# 8pins_together.net
KiCad netlist of a schematic drawn in Altium Designer
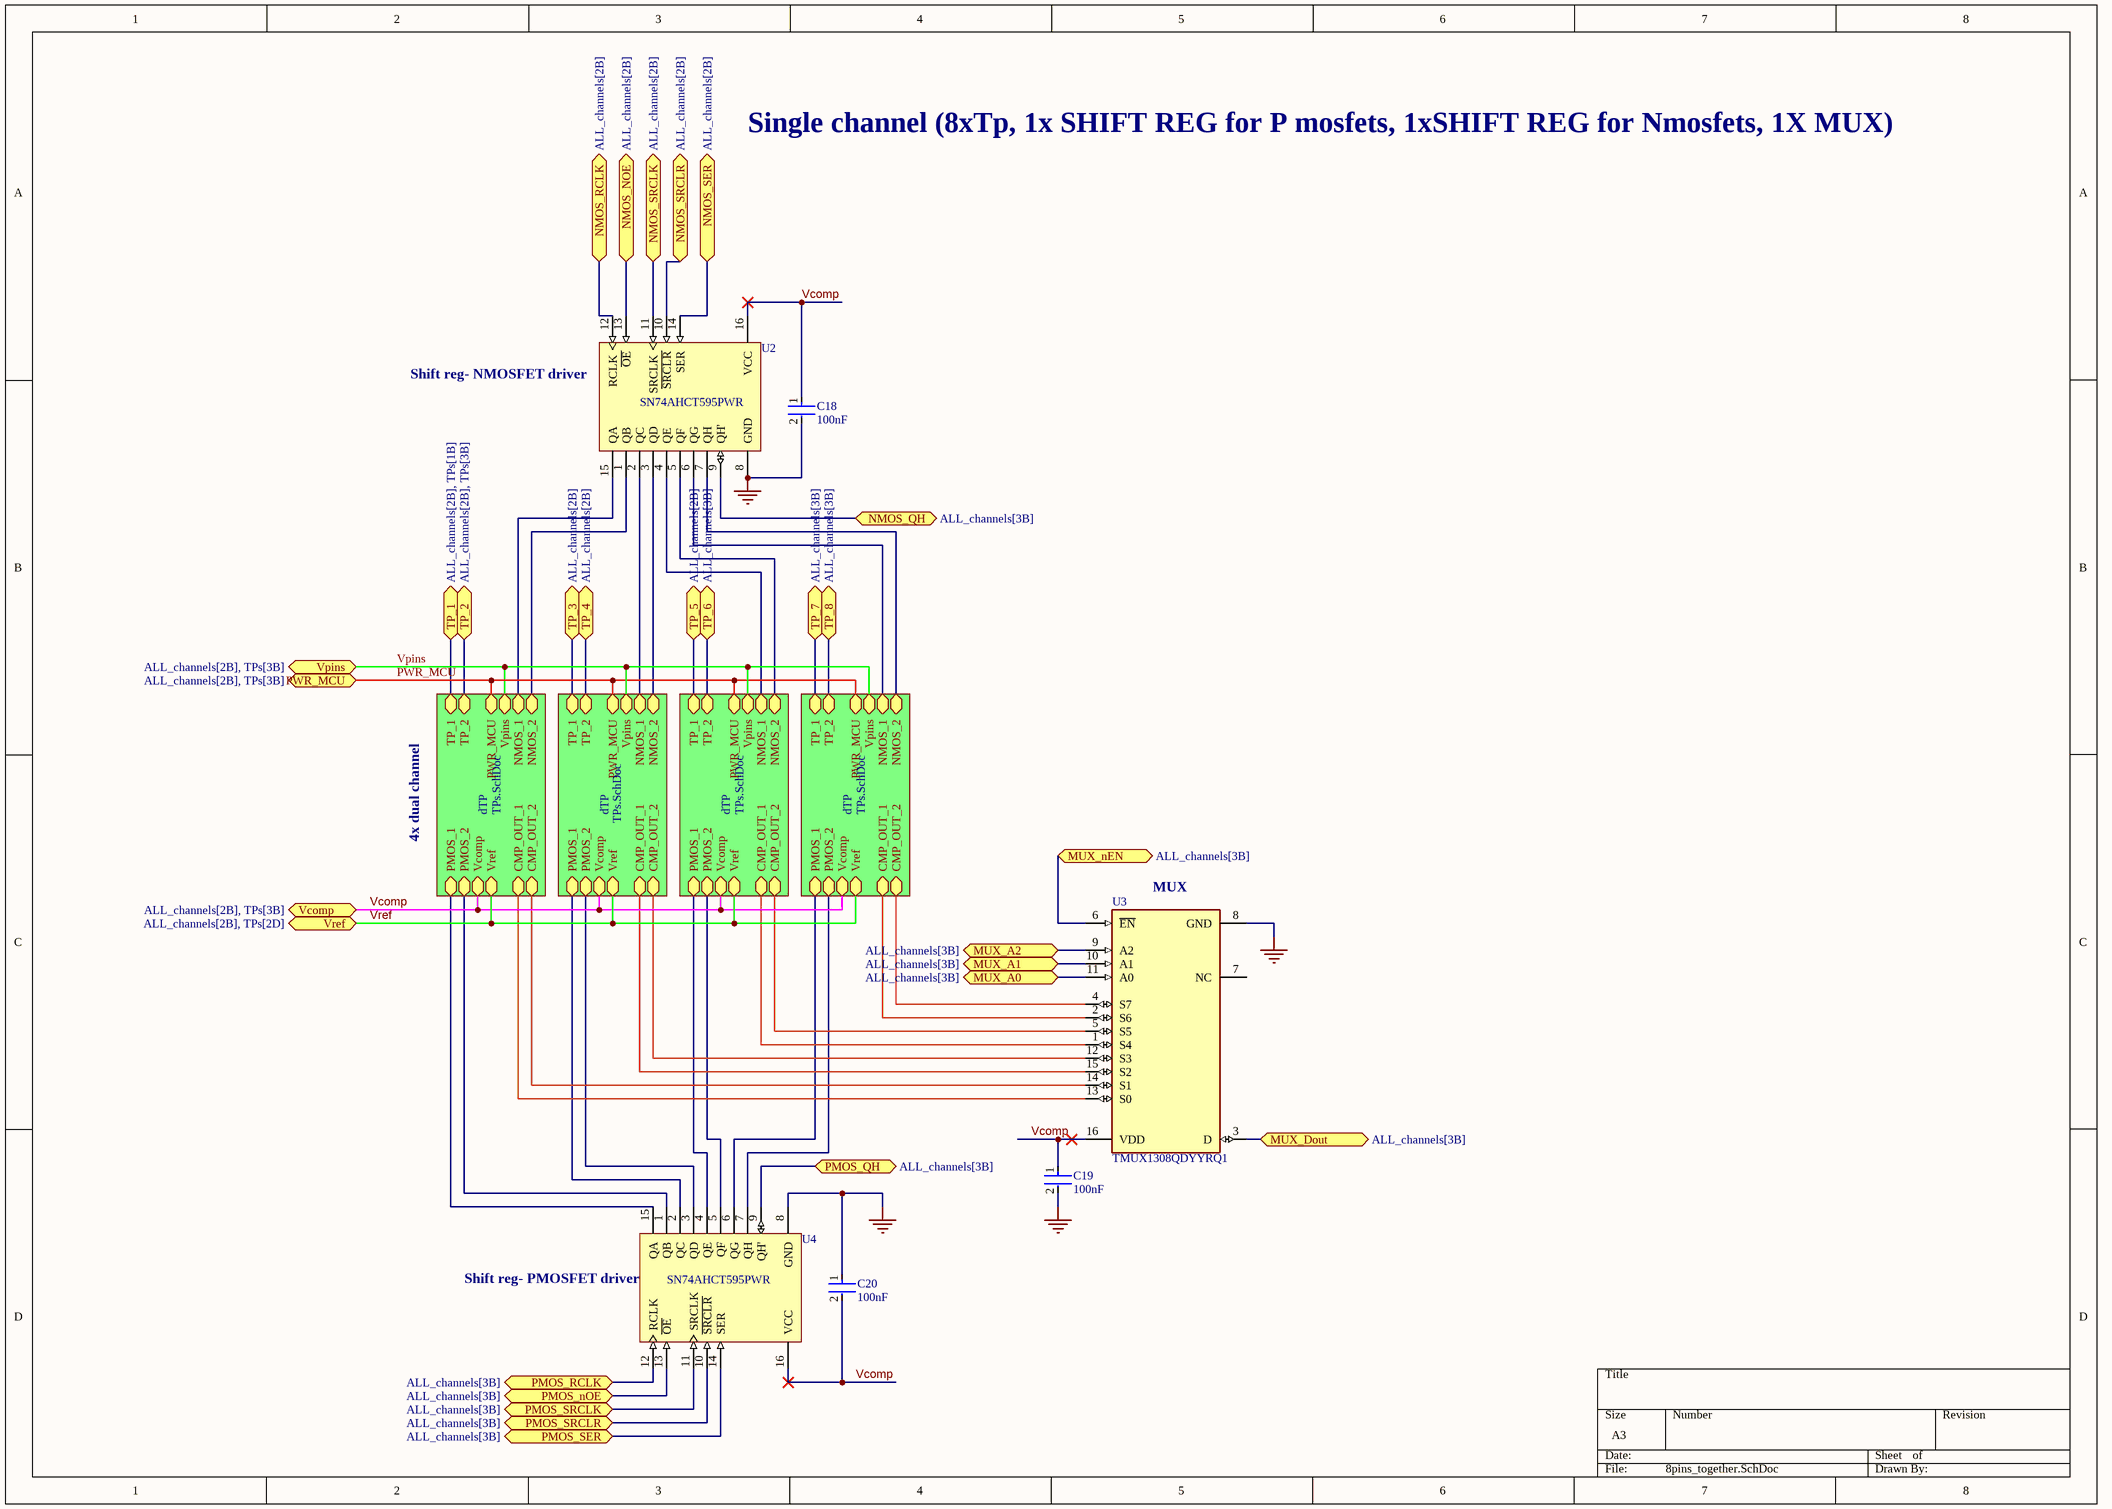
[diagram p0: 8pins_together.SchDoc]

(export (version "E")
  (design (tool "Eeschema 10.0.6"))
  (components
    (comp (ref "C18")
      (value "100nF")
      (footprint "PcbLib1:0402 CAP")
      (description "Cap Ceramic 0.1uF 25V X7R 10% Pad SMD 0402 125C T/R")
      (fields
        (field (name "MANUFACTURER") "Kemet")
        (field (name "MANUFACTURER PART NUMBER") "C0402C104K3RACTU")
      )
      (libsource (lib "Schlib1") (part "Capacitor 0402 25V"))
    )
    (comp (ref "C19")
      (value "100nF")
      (footprint "PcbLib1:0402 CAP")
      (description "Cap Ceramic 0.1uF 25V X7R 10% Pad SMD 0402 125C T/R")
      (fields
        (field (name "MANUFACTURER") "Kemet")
        (field (name "MANUFACTURER PART NUMBER") "C0402C104K3RACTU")
      )
      (libsource (lib "Schlib1") (part "Capacitor 0402 25V"))
    )
    (comp (ref "C20")
      (value "100nF")
      (footprint "PcbLib1:0402 CAP")
      (description "Cap Ceramic 0.1uF 25V X7R 10% Pad SMD 0402 125C T/R")
      (fields
        (field (name "MANUFACTURER") "Kemet")
        (field (name "MANUFACTURER PART NUMBER") "C0402C104K3RACTU")
      )
      (libsource (lib "Schlib1") (part "Capacitor 0402 25V"))
    )
    (comp (ref "U2")
      (value "SN74AHCT595PWR")
      (footprint "PcbLib1:SSOT16")
      (description "8-Bit Shift Registers With 3-State Output Registers, PW0016A, LARGE T&R")
      (fields
        (field (name "GENERIC PART NUMBER") "SN74AHCT595")
        (field (name "MANUFACTURER") "Texas Instruments")
      )
      (libsource (lib "") (part "SN74AHCT595PWR_1"))
    )
    (comp (ref "U3")
      (value "TMUX1308QDYYRQ1")
      (footprint "PcbLib1:FP-DYY0016A-MFG")
      (description "AUTOMOTIVE, 5-V, 8:1, 1-CHANNEL")
      (libsource (lib "Schlib1") (part "TMUX1308QDYYRQ1"))
    )
    (comp (ref "U4")
      (value "SN74AHCT595PWR")
      (footprint "PcbLib1:SSOT16")
      (description "8-Bit Shift Registers With 3-State Output Registers, PW0016A, LARGE T&R")
      (fields
        (field (name "GENERIC PART NUMBER") "SN74AHCT595")
        (field (name "MANUFACTURER") "Texas Instruments")
      )
      (libsource (lib "Schlib1") (part "SN74AHCT595PWR"))
    )
  )
  (nets
    (net (code "1") (name "/CMP_OUT_1") (class "Default")
      (node (ref "U3") (pin "1") (pinfunction "S4_1") (pintype "bidirectional"))
    )
    (net (code "2") (name "/CMP_OUT_1_1") (class "Default")
      (node (ref "U3") (pin "2") (pinfunction "S6_2") (pintype "bidirectional"))
    )
    (net (code "3") (name "/CMP_OUT_1_2") (class "Default")
      (node (ref "U3") (pin "13") (pinfunction "S0_13") (pintype "bidirectional"))
    )
    (net (code "4") (name "/CMP_OUT_1_3") (class "Default")
      (node (ref "U3") (pin "15") (pinfunction "S2_15") (pintype "bidirectional"))
    )
    (net (code "5") (name "/CMP_OUT_2") (class "Default")
      (node (ref "U3") (pin "5") (pinfunction "S5_5") (pintype "bidirectional"))
    )
    (net (code "6") (name "/CMP_OUT_2_1") (class "Default")
      (node (ref "U3") (pin "4") (pinfunction "S7_4") (pintype "bidirectional"))
    )
    (net (code "7") (name "/CMP_OUT_2_2") (class "Default")
      (node (ref "U3") (pin "14") (pinfunction "S1_14") (pintype "bidirectional"))
    )
    (net (code "8") (name "/CMP_OUT_2_3") (class "Default")
      (node (ref "U3") (pin "12") (pinfunction "S3_12") (pintype "bidirectional"))
    )
    (net (code "9") (name "/MUX_A0") (class "Default")
      (node (ref "U3") (pin "11") (pinfunction "A0_11") (pintype "input"))
    )
    (net (code "10") (name "/MUX_A1") (class "Default")
      (node (ref "U3") (pin "10") (pinfunction "A1_10") (pintype "input"))
    )
    (net (code "11") (name "/MUX_A2") (class "Default")
      (node (ref "U3") (pin "9") (pinfunction "A2_9") (pintype "input"))
    )
    (net (code "12") (name "/MUX_Dout") (class "Default")
      (node (ref "U3") (pin "3") (pinfunction "D_3") (pintype "bidirectional"))
    )
    (net (code "13") (name "/MUX_nEN") (class "Default")
      (node (ref "U3") (pin "6") (pinfunction "~{EN}_6") (pintype "input"))
    )
    (net (code "14") (name "/NMOS_1") (class "Default")
      (node (ref "U2") (pin "2") (pinfunction "QC_2") (pintype "tri_state"))
    )
    (net (code "15") (name "/NMOS_1_1") (class "Default")
      (node (ref "U2") (pin "4") (pinfunction "QE_4") (pintype "tri_state"))
    )
    (net (code "16") (name "/NMOS_1_2") (class "Default")
      (node (ref "U2") (pin "6") (pinfunction "QG_6") (pintype "tri_state"))
    )
    (net (code "17") (name "/NMOS_1_3") (class "Default")
      (node (ref "U2") (pin "15") (pinfunction "QA_15") (pintype "tri_state"))
    )
    (net (code "18") (name "/NMOS_2") (class "Default")
      (node (ref "U2") (pin "3") (pinfunction "QD_3") (pintype "tri_state"))
    )
    (net (code "19") (name "/NMOS_2_1") (class "Default")
      (node (ref "U2") (pin "5") (pinfunction "QF_5") (pintype "tri_state"))
    )
    (net (code "20") (name "/NMOS_2_2") (class "Default")
      (node (ref "U2") (pin "7") (pinfunction "QH_7") (pintype "tri_state"))
    )
    (net (code "21") (name "/NMOS_2_3") (class "Default")
      (node (ref "U2") (pin "1") (pinfunction "QB_1") (pintype "tri_state"))
    )
    (net (code "22") (name "/NMOS_NOE") (class "Default")
      (node (ref "U2") (pin "13") (pinfunction "~{OE}_13") (pintype "input"))
    )
    (net (code "23") (name "/NMOS_QH") (class "Default")
      (node (ref "U2") (pin "9") (pinfunction "QH'_9") (pintype "bidirectional"))
    )
    (net (code "24") (name "/NMOS_RCLK") (class "Default")
      (node (ref "U2") (pin "12") (pinfunction "RCLK_12") (pintype "input"))
    )
    (net (code "25") (name "/NMOS_SER") (class "Default")
      (node (ref "U2") (pin "14") (pinfunction "SER_14") (pintype "input"))
    )
    (net (code "26") (name "/NMOS_SRCLK") (class "Default")
      (node (ref "U2") (pin "11") (pinfunction "SRCLK_11") (pintype "input"))
    )
    (net (code "27") (name "/NMOS_SRCLR") (class "Default")
      (node (ref "U2") (pin "10") (pinfunction "~{SRCLR}_10") (pintype "input"))
    )
    (net (code "28") (name "/PMOS_1") (class "Default")
      (node (ref "U4") (pin "4") (pinfunction "QE_4") (pintype "tri_state"))
    )
    (net (code "29") (name "/PMOS_1_1") (class "Default")
      (node (ref "U4") (pin "6") (pinfunction "QG_6") (pintype "tri_state"))
    )
    (net (code "30") (name "/PMOS_1_2") (class "Default")
      (node (ref "U4") (pin "15") (pinfunction "QA_15") (pintype "tri_state"))
    )
    (net (code "31") (name "/PMOS_1_3") (class "Default")
      (node (ref "U4") (pin "2") (pinfunction "QC_2") (pintype "tri_state"))
    )
    (net (code "32") (name "/PMOS_2") (class "Default")
      (node (ref "U4") (pin "5") (pinfunction "QF_5") (pintype "tri_state"))
    )
    (net (code "33") (name "/PMOS_2_1") (class "Default")
      (node (ref "U4") (pin "7") (pinfunction "QH_7") (pintype "tri_state"))
    )
    (net (code "34") (name "/PMOS_2_2") (class "Default")
      (node (ref "U4") (pin "1") (pinfunction "QB_1") (pintype "tri_state"))
    )
    (net (code "35") (name "/PMOS_2_3") (class "Default")
      (node (ref "U4") (pin "3") (pinfunction "QD_3") (pintype "tri_state"))
    )
    (net (code "36") (name "/PMOS_QH") (class "Default")
      (node (ref "U4") (pin "9") (pinfunction "QH'_9") (pintype "bidirectional"))
    )
    (net (code "37") (name "/PMOS_RCLK") (class "Default")
      (node (ref "U4") (pin "12") (pinfunction "RCLK_12") (pintype "input"))
    )
    (net (code "38") (name "/PMOS_SER") (class "Default")
      (node (ref "U4") (pin "14") (pinfunction "SER_14") (pintype "input"))
    )
    (net (code "39") (name "/PMOS_SRCLK") (class "Default")
      (node (ref "U4") (pin "11") (pinfunction "SRCLK_11") (pintype "input"))
    )
    (net (code "40") (name "/PMOS_SRCLR") (class "Default")
      (node (ref "U4") (pin "10") (pinfunction "~{SRCLR}_10") (pintype "input"))
    )
    (net (code "41") (name "/PMOS_nOE") (class "Default")
      (node (ref "U4") (pin "13") (pinfunction "~{OE}_13") (pintype "input"))
    )
    (net (code "51") (name "/Vcomp") (class "Default")
      (node (ref "C18") (pin "1") (pinfunction "1_1") (pintype "passive"))
      (node (ref "C19") (pin "1") (pinfunction "1_1") (pintype "passive"))
      (node (ref "C20") (pin "2") (pinfunction "2_2") (pintype "passive"))
      (node (ref "U2") (pin "16") (pinfunction "VCC_16") (pintype "power_in"))
      (node (ref "U3") (pin "16") (pinfunction "VDD_16") (pintype "power_in"))
      (node (ref "U4") (pin "16") (pinfunction "VCC_16") (pintype "power_in"))
    )
    (net (code "54") (name "GND") (class "Default")
      (node (ref "C18") (pin "2") (pinfunction "2_2") (pintype "passive"))
      (node (ref "C19") (pin "2") (pinfunction "2_2") (pintype "passive"))
      (node (ref "C20") (pin "1") (pinfunction "1_1") (pintype "passive"))
      (node (ref "U2") (pin "8") (pinfunction "GND_8") (pintype "power_in"))
      (node (ref "U3") (pin "8") (pinfunction "GND_8") (pintype "power_in"))
      (node (ref "U4") (pin "8") (pinfunction "GND_8") (pintype "power_in"))
    )
    (net (code "55") (name "unconnected-(U3-NC-Pad7)") (class "Default")
      (node (ref "U3") (pin "7") (pinfunction "NC_7") (pintype "passive"))
    )
  )
)
